# 3V3_LDO.net
KiCad netlist of a schematic drawn in Altium Designer
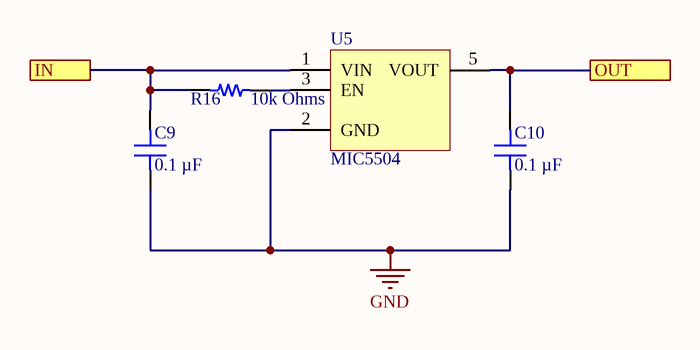
[diagram p0: 3V3_LDO.SchDoc]

(export (version "E")
  (design (tool "Eeschema 10.0.6"))
  (components
    (comp (ref "C9")
      (value "0.1 µF")
      (footprint "CAP 0402_1005")
      (description "CAP CER 0.1UF 16V X7R 0402")
      (fields (field (name "PART NUMBER") "C0402C104K4RACAUTO") (field (name "MANUFACTURER") "KEMET"))
      (libsource (lib "Celestial Altium Library - altium_library") (part "Capacitor"))
    )
    (comp (ref "C10")
      (value "0.1 µF")
      (footprint "CAP 0402_1005")
      (description "CAP CER 0.1UF 16V X7R 0402")
      (fields (field (name "PART NUMBER") "C0402C104K4RACAUTO") (field (name "MANUFACTURER") "KEMET"))
      (libsource (lib "Celestial Altium Library - altium_library") (part "Capacitor"))
    )
    (comp (ref "R16")
      (value "10k Ohms")
      (footprint "RES 0402_1005")
      (description "RES 330 OHM 5% 1/16W 0402")
      (fields (field (name "PART NUMBER") "CRCW0402330RJNEDC") (field (name "MANUFACTURER") "Vishay Dale"))
      (libsource (lib "Celestial Altium Library - altium_library") (part "Resistor"))
    )
    (comp (ref "U5")
      (value "MIC5504")
      (footprint "TI SOT-23-5 DBV")
      (description "3.3V LDO")
      (libsource (lib "IC") (part "MIC5504-3.3YM5"))
    )
  )
  (nets
    (net (code "1") (name "/IN") (class "Default")
      (node (ref "C9") (pin "2") (pinfunction "2_2") (pintype "passive"))
      (node (ref "R16") (pin "2") (pinfunction "2_2") (pintype "passive"))
      (node (ref "U5") (pin "1") (pinfunction "VIN_1") (pintype "passive"))
    )
    (net (code "2") (name "/OUT") (class "Default")
      (node (ref "C10") (pin "2") (pinfunction "2_2") (pintype "passive"))
      (node (ref "U5") (pin "5") (pinfunction "VOUT_5") (pintype "passive"))
    )
    (net (code "3") (name "GND") (class "Default")
      (node (ref "C10") (pin "1") (pinfunction "1_1") (pintype "passive"))
      (node (ref "C9") (pin "1") (pinfunction "1_1") (pintype "passive"))
      (node (ref "U5") (pin "2") (pinfunction "GND_2") (pintype "passive"))
    )
    (net (code "4") (name "Net-(U5-EN)") (class "Default")
      (node (ref "R16") (pin "1") (pinfunction "1_1") (pintype "passive"))
      (node (ref "U5") (pin "3") (pinfunction "EN_3") (pintype "passive"))
    )
  )
)
